# Sheet1.net
KiCad netlist of a schematic drawn in Altium Designer
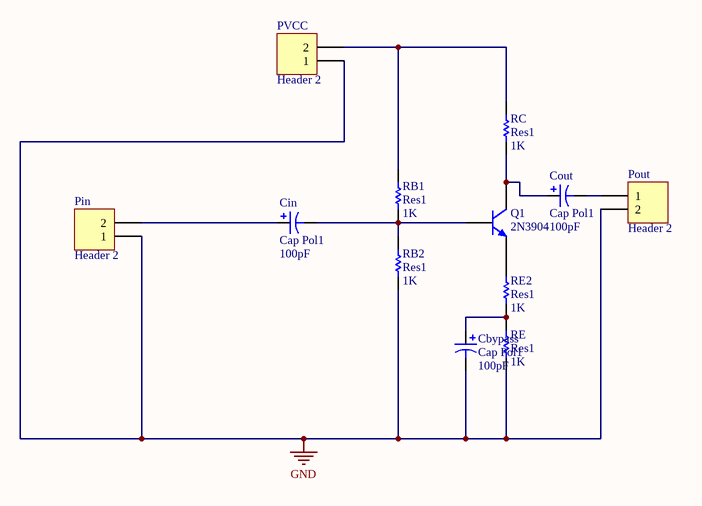
[diagram p0: Sheet1.SchDoc]

(export (version "E")
  (design (tool "Eeschema 10.0.6"))
  (components
    (comp (ref "Cbypass")
      (value "Cap Pol1")
      (footprint "RB7.6-15")
      (description "Polarized Capacitor (Radial)")
      (fields (field (name "ALTIUM_VALUE") "100pF") (field (name "PUBLISHER") "Altium Limited"))
      (libsource (lib "Miscellaneous Devices") (part "Cap Pol1"))
    )
    (comp (ref "Cin")
      (value "Cap Pol1")
      (footprint "RB7.6-15")
      (description "Polarized Capacitor (Radial)")
      (fields (field (name "ALTIUM_VALUE") "100pF") (field (name "PUBLISHER") "Altium Limited"))
      (libsource (lib "Miscellaneous Devices") (part "Cap Pol1"))
    )
    (comp (ref "Cout")
      (value "Cap Pol1")
      (footprint "RB7.6-15")
      (description "Polarized Capacitor (Radial)")
      (fields (field (name "ALTIUM_VALUE") "100pF") (field (name "PUBLISHER") "Altium Limited"))
      (libsource (lib "Miscellaneous Devices") (part "Cap Pol1"))
    )
    (comp (ref "Pin")
      (value "Header 2")
      (footprint "HDR1X2")
      (description "Header, 2-Pin")
      (fields (field (name "PUBLISHER") "Altium Limited"))
      (libsource (lib "") (part "Header 2_1"))
    )
    (comp (ref "Pout")
      (value "Header 2")
      (footprint "HDR1X2")
      (description "Header, 2-Pin")
      (fields (field (name "PUBLISHER") "Altium Limited"))
      (libsource (lib "Miscellaneous Connectors") (part "Header 2"))
    )
    (comp (ref "PVCC")
      (value "Header 2")
      (footprint "HDR1X2")
      (description "Header, 2-Pin")
      (fields (field (name "PUBLISHER") "Altium Limited"))
      (libsource (lib "") (part "Header 2_1"))
    )
    (comp (ref "Q1")
      (value "2N3904")
      (footprint "TO-92A")
      (description "NPN General Purpose Amplifier")
      (fields (field (name "PUBLISHER") "Altium Limited"))
      (libsource (lib "Miscellaneous Devices") (part "2N3904"))
    )
    (comp (ref "RB1")
      (value "Res1")
      (footprint "AXIAL-0.3")
      (description "Resistor")
      (fields (field (name "ALTIUM_VALUE") "1K") (field (name "PUBLISHER") "Altium Limited"))
      (libsource (lib "Miscellaneous Devices") (part "Res1"))
    )
    (comp (ref "RB2")
      (value "Res1")
      (footprint "AXIAL-0.3")
      (description "Resistor")
      (fields (field (name "ALTIUM_VALUE") "1K") (field (name "PUBLISHER") "Altium Limited"))
      (libsource (lib "Miscellaneous Devices") (part "Res1"))
    )
    (comp (ref "RC")
      (value "Res1")
      (footprint "AXIAL-0.3")
      (description "Resistor")
      (fields (field (name "ALTIUM_VALUE") "1K") (field (name "PUBLISHER") "Altium Limited"))
      (libsource (lib "Miscellaneous Devices") (part "Res1"))
    )
    (comp (ref "RE")
      (value "Res1")
      (footprint "AXIAL-0.3")
      (description "Resistor")
      (fields (field (name "ALTIUM_VALUE") "1K") (field (name "PUBLISHER") "Altium Limited"))
      (libsource (lib "Miscellaneous Devices") (part "Res1"))
    )
    (comp (ref "RE2")
      (value "Res1")
      (footprint "AXIAL-0.3")
      (description "Resistor")
      (fields (field (name "ALTIUM_VALUE") "1K") (field (name "PUBLISHER") "Altium Limited"))
      (libsource (lib "Miscellaneous Devices") (part "Res1"))
    )
  )
  (nets
    (net (code "1") (name "GND") (class "Default")
      (node (ref "Cbypass") (pin "2") (pinfunction "2_2") (pintype "passive"))
      (node (ref "PVCC") (pin "1") (pinfunction "1_1") (pintype "passive"))
      (node (ref "Pin") (pin "1") (pinfunction "1_1") (pintype "passive"))
      (node (ref "Pout") (pin "2") (pinfunction "2_2") (pintype "passive"))
      (node (ref "RB2") (pin "1") (pinfunction "1_1") (pintype "passive"))
      (node (ref "RE") (pin "1") (pinfunction "1_1") (pintype "passive"))
    )
    (net (code "2") (name "Net-(Cbypass-Pad1)") (class "Default")
      (node (ref "Cbypass") (pin "1") (pinfunction "1_1") (pintype "passive"))
      (node (ref "RE") (pin "2") (pinfunction "2_2") (pintype "passive"))
      (node (ref "RE2") (pin "1") (pinfunction "1_1") (pintype "passive"))
    )
    (net (code "3") (name "Net-(Cin-Pad1)") (class "Default")
      (node (ref "Cin") (pin "1") (pinfunction "1_1") (pintype "passive"))
      (node (ref "Pin") (pin "2") (pinfunction "2_2") (pintype "passive"))
    )
    (net (code "4") (name "Net-(Cout-Pad2)") (class "Default")
      (node (ref "Cout") (pin "2") (pinfunction "2_2") (pintype "passive"))
      (node (ref "Pout") (pin "1") (pinfunction "1_1") (pintype "passive"))
    )
    (net (code "5") (name "Net-(PVCC-Pad2)") (class "Default")
      (node (ref "PVCC") (pin "2") (pinfunction "2_2") (pintype "passive"))
      (node (ref "RB1") (pin "2") (pinfunction "2_2") (pintype "passive"))
      (node (ref "RC") (pin "2") (pinfunction "2_2") (pintype "passive"))
    )
    (net (code "6") (name "Net-(Q1-B)") (class "Default")
      (node (ref "Cin") (pin "2") (pinfunction "2_2") (pintype "passive"))
      (node (ref "Q1") (pin "2") (pinfunction "B_2") (pintype "passive"))
      (node (ref "RB1") (pin "1") (pinfunction "1_1") (pintype "passive"))
      (node (ref "RB2") (pin "2") (pinfunction "2_2") (pintype "passive"))
    )
    (net (code "7") (name "Net-(Q1-C)") (class "Default")
      (node (ref "Cout") (pin "1") (pinfunction "1_1") (pintype "passive"))
      (node (ref "Q1") (pin "3") (pinfunction "C_3") (pintype "passive"))
      (node (ref "RC") (pin "1") (pinfunction "1_1") (pintype "passive"))
    )
    (net (code "8") (name "Net-(Q1-E)") (class "Default")
      (node (ref "Q1") (pin "1") (pinfunction "E_1") (pintype "passive"))
      (node (ref "RE2") (pin "2") (pinfunction "2_2") (pintype "passive"))
    )
  )
)
